# SensorStick.net
KiCad netlist of a schematic drawn in EAGLE
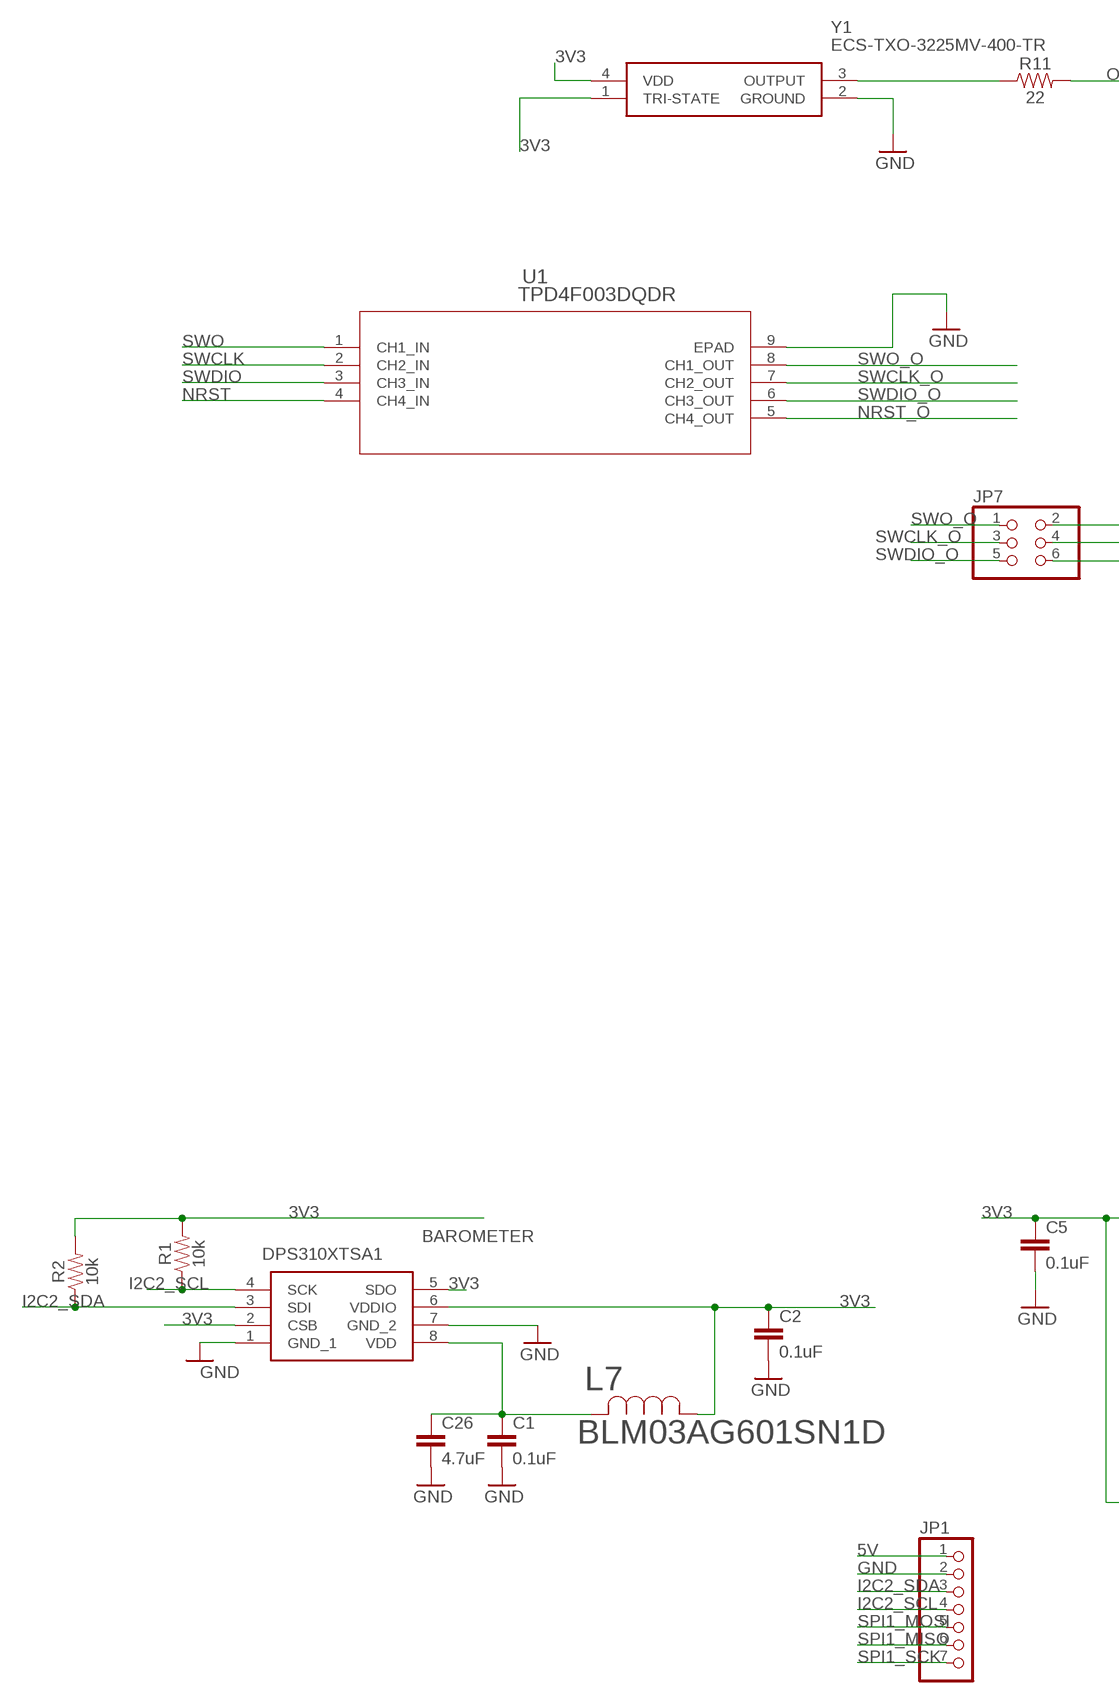
[diagram p0: schematic, sheet 1, part 1 of 2]
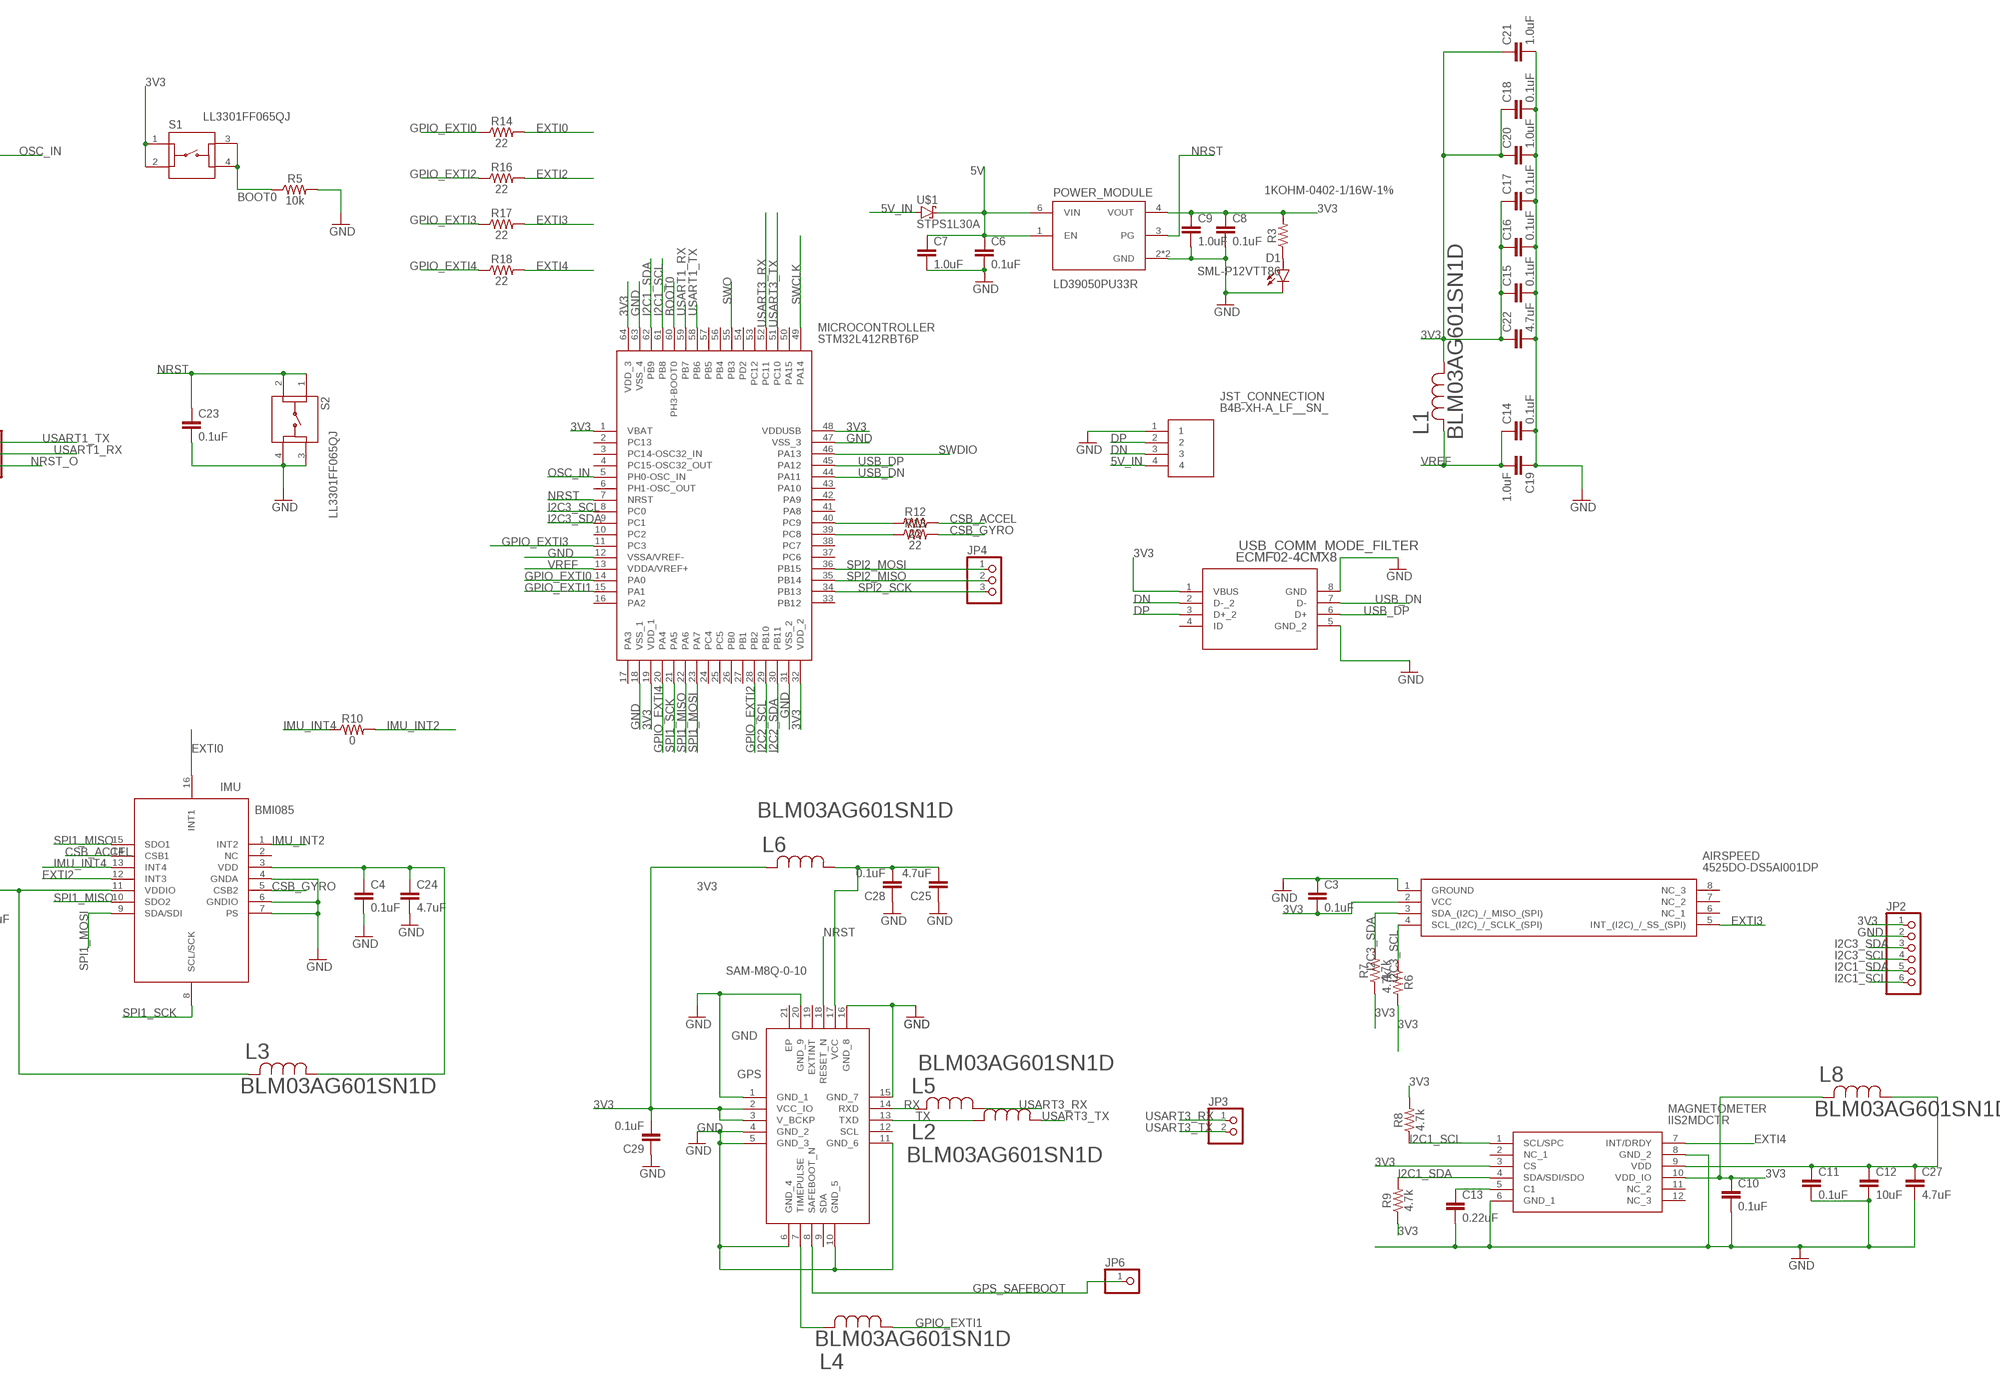
[diagram p1: schematic, sheet 1, part 2 of 2]

(export (version "E")
  (design (tool "Eeschema 10.0.6"))
  (components
    (comp (ref "AIRSPEED")
      (value "4525DO-DS5AI001DP")
      (footprint "eagle-import:4525DO-DS...P")
      (fields (field (name "MOUSER_PART_NUMBER") "824-4525DODS5AI001DP"))
      (libsource (lib "eagle-import") (part "4525DO-DS5AI001DP"))
    )
    (comp (ref "BAROMETER")
      (value "DPS310XTSA1")
      (footprint "eagle-import:DPS310XTSA1")
      (fields (field (name "MOUSER_PART_NUMBER") "726-DPS310XTSA1"))
      (libsource (lib "eagle-import") (part "DPS310XTSA1"))
    )
    (comp (ref "C1")
      (value "0.1uF")
      (footprint "eagle-import:0402")
      (libsource (lib "eagle-import") (part "0.1UF-0402-6.3V-10%-X7R"))
    )
    (comp (ref "C2")
      (value "0.1uF")
      (footprint "eagle-import:0402")
      (libsource (lib "eagle-import") (part "0.1UF-0402-6.3V-10%-X7R"))
    )
    (comp (ref "C3")
      (value "0.1uF")
      (footprint "eagle-import:0402")
      (fields (field (name "SPICEPREFIX") "C"))
      (libsource (lib "eagle-import") (part "0.1UF-0402-6.3V-10%-X7R"))
    )
    (comp (ref "C4")
      (value "0.1uF")
      (footprint "eagle-import:0402")
      (libsource (lib "eagle-import") (part "0.1UF-0402-6.3V-10%-X7R"))
    )
    (comp (ref "C5")
      (value "0.1uF")
      (footprint "eagle-import:0402")
      (libsource (lib "eagle-import") (part "0.1UF-0402-6.3V-10%-X7R"))
    )
    (comp (ref "C6")
      (value "0.1uF")
      (footprint "eagle-import:0402")
      (libsource (lib "eagle-import") (part "0.1UF-0402-6.3V-10%-X7R"))
    )
    (comp (ref "C7")
      (value "1.0uF")
      (footprint "eagle-import:0402")
      (libsource (lib "eagle-import") (part "1.0UF-0402-16V-10%"))
    )
    (comp (ref "C8")
      (value "0.1uF")
      (footprint "eagle-import:0402")
      (libsource (lib "eagle-import") (part "0.1UF-0402-6.3V-10%-X7R"))
    )
    (comp (ref "C9")
      (value "1.0uF")
      (footprint "eagle-import:0402")
      (libsource (lib "eagle-import") (part "1.0UF-0402-16V-10%"))
    )
    (comp (ref "C10")
      (value "0.1uF")
      (footprint "eagle-import:0402")
      (libsource (lib "eagle-import") (part "0.1UF-0402-6.3V-10%-X7R"))
    )
    (comp (ref "C11")
      (value "0.1uF")
      (footprint "eagle-import:0402")
      (libsource (lib "eagle-import") (part "0.1UF-0402-6.3V-10%-X7R"))
    )
    (comp (ref "C12")
      (value "10uF")
      (footprint "eagle-import:0603")
      (libsource (lib "eagle-import") (part "10UF-0603-6.3V-20%"))
    )
    (comp (ref "C13")
      (value "0.22uF")
      (footprint "eagle-import:0603")
      (libsource (lib "eagle-import") (part "0.22UF-0603-25V-10%"))
    )
    (comp (ref "C14")
      (value "0.1uF")
      (footprint "eagle-import:0603")
      (libsource (lib "eagle-import") (part "SparkFun-Capacitors_510_0.1UF-0603-25V-5%"))
    )
    (comp (ref "C15")
      (value "0.1uF")
      (footprint "eagle-import:0603")
      (libsource (lib "eagle-import") (part "SparkFun-Capacitors_510_0.1UF-0603-25V-5%"))
    )
    (comp (ref "C16")
      (value "0.1uF")
      (footprint "eagle-import:0603")
      (libsource (lib "eagle-import") (part "SparkFun-Capacitors_510_0.1UF-0603-25V-5%"))
    )
    (comp (ref "C17")
      (value "0.1uF")
      (footprint "eagle-import:0603")
      (libsource (lib "eagle-import") (part "SparkFun-Capacitors_510_0.1UF-0603-25V-5%"))
    )
    (comp (ref "C18")
      (value "0.1uF")
      (footprint "eagle-import:0603")
      (libsource (lib "eagle-import") (part "SparkFun-Capacitors_510_0.1UF-0603-25V-5%"))
    )
    (comp (ref "C19")
      (value "1.0uF")
      (footprint "eagle-import:0805")
      (libsource (lib "eagle-import") (part "SparkFun-Capacitors_510_1.0UF-0805-25V-10%"))
    )
    (comp (ref "C20")
      (value "1.0uF")
      (footprint "eagle-import:0805")
      (libsource (lib "eagle-import") (part "SparkFun-Capacitors_510_1.0UF-0805-25V-10%"))
    )
    (comp (ref "C21")
      (value "1.0uF")
      (footprint "eagle-import:0805")
      (libsource (lib "eagle-import") (part "SparkFun-Capacitors_510_1.0UF-0805-25V-10%"))
    )
    (comp (ref "C22")
      (value "4.7uF")
      (footprint "eagle-import:0603")
      (libsource (lib "eagle-import") (part "4.7UF0603"))
    )
    (comp (ref "C23")
      (value "0.1uF")
      (footprint "eagle-import:0603")
      (libsource (lib "eagle-import") (part "SparkFun-Capacitors_510_0.1UF-0603-25V-5%"))
    )
    (comp (ref "C24")
      (value "4.7uF")
      (footprint "eagle-import:0603")
      (libsource (lib "eagle-import") (part "4.7UF0603"))
    )
    (comp (ref "C25")
      (value "4.7uF")
      (footprint "eagle-import:0603")
      (libsource (lib "eagle-import") (part "4.7UF0603"))
    )
    (comp (ref "C26")
      (value "4.7uF")
      (footprint "eagle-import:0603")
      (libsource (lib "eagle-import") (part "4.7UF0603"))
    )
    (comp (ref "C27")
      (value "4.7uF")
      (footprint "eagle-import:0603")
      (libsource (lib "eagle-import") (part "4.7UF0603"))
    )
    (comp (ref "C28")
      (value "0.1uF")
      (footprint "eagle-import:0402")
      (libsource (lib "eagle-import") (part "SparkFun-Capacitors_510_0.1UF-0402-16V-10%"))
    )
    (comp (ref "C29")
      (value "0.1uF")
      (footprint "eagle-import:0402")
      (libsource (lib "eagle-import") (part "SparkFun-Capacitors_510_0.1UF-0402-16V-10%"))
    )
    (comp (ref "D1")
      (value "SML-P12VTT86")
      (footprint "eagle-import:LED_SML-P11UTT86R")
      (fields (field (name "MF") "Rohm"))
      (libsource (lib "eagle-import") (part "SML-P12VTT86"))
    )
    (comp (ref "GPS")
      (value "SAM-M8Q-0-10")
      (footprint "eagle-import:SAMM8Q010")
      (libsource (lib "eagle-import") (part "SAM-M8Q-0-10"))
    )
    (comp (ref "IMU")
      (value "BMI085")
      (footprint "eagle-import:BMI085")
      (fields (field (name "MOUSER_PART_NUMBER") "262-BMI085"))
      (libsource (lib "eagle-import") (part "BMI085"))
    )
    (comp (ref "JP1")
      (value "PINHD-1X7")
      (footprint "eagle-import:1X07")
      (libsource (lib "eagle-import") (part "PINHD-1X7"))
    )
    (comp (ref "JP2")
      (value "PINHD-1X6")
      (footprint "eagle-import:1X06")
      (libsource (lib "eagle-import") (part "PINHD-1X6"))
    )
    (comp (ref "JP3")
      (value "PINHD-1X2")
      (footprint "eagle-import:1X02")
      (libsource (lib "eagle-import") (part "PINHD-1X2"))
    )
    (comp (ref "JP4")
      (value "PINHD-1X3")
      (footprint "eagle-import:1X03")
      (libsource (lib "eagle-import") (part "PINHD-1X3"))
    )
    (comp (ref "JP6")
      (value "PINHD-1X1")
      (footprint "eagle-import:1X01")
      (libsource (lib "eagle-import") (part "PINHD-1X1"))
    )
    (comp (ref "JP7")
      (value "PINHD-2X3")
      (footprint "eagle-import:2X03")
      (libsource (lib "eagle-import") (part "PINHD-2X3"))
    )
    (comp (ref "JST_CONNECTION")
      (value "B4B-XH-A_LF__SN_")
      (footprint "eagle-import:B4BXHALFSN")
      (fields (field (name "ARROW_PART_NUMBER") "B4B-XH-A(LF)(SN)"))
      (libsource (lib "eagle-import") (part "B4B-XH-A_LF__SN_"))
    )
    (comp (ref "L1")
      (value "BLM03AG601SN1D")
      (footprint "eagle-import:IND_BLM03_0201_MUR")
      (fields (field (name "COPYRIGHT") "Copyright (C) 2023 Ultra Librarian. All rights reserved."))
      (libsource (lib "eagle-import") (part "BLM03AG601SN1D"))
    )
    (comp (ref "L2")
      (value "BLM03AG601SN1D")
      (footprint "eagle-import:IND_BLM03_0201_MUR")
      (fields (field (name "COPYRIGHT") "Copyright (C) 2023 Ultra Librarian. All rights reserved."))
      (libsource (lib "eagle-import") (part "BLM03AG601SN1D"))
    )
    (comp (ref "L3")
      (value "BLM03AG601SN1D")
      (footprint "eagle-import:IND_BLM03_0201_MUR")
      (fields (field (name "COPYRIGHT") "Copyright (C) 2023 Ultra Librarian. All rights reserved."))
      (libsource (lib "eagle-import") (part "BLM03AG601SN1D"))
    )
    (comp (ref "L4")
      (value "BLM03AG601SN1D")
      (footprint "eagle-import:IND_BLM03_0201_MUR")
      (fields (field (name "COPYRIGHT") "Copyright (C) 2023 Ultra Librarian. All rights reserved."))
      (libsource (lib "eagle-import") (part "BLM03AG601SN1D"))
    )
    (comp (ref "L5")
      (value "BLM03AG601SN1D")
      (footprint "eagle-import:IND_BLM03_0201_MUR")
      (fields (field (name "COPYRIGHT") "Copyright (C) 2023 Ultra Librarian. All rights reserved."))
      (libsource (lib "eagle-import") (part "BLM03AG601SN1D"))
    )
    (comp (ref "L6")
      (value "BLM03AG601SN1D")
      (footprint "eagle-import:IND_BLM03_0201_MUR")
      (fields (field (name "COPYRIGHT") "Copyright (C) 2023 Ultra Librarian. All rights reserved."))
      (libsource (lib "eagle-import") (part "BLM03AG601SN1D"))
    )
    (comp (ref "L7")
      (value "BLM03AG601SN1D")
      (footprint "eagle-import:IND_BLM03_0201_MUR")
      (fields (field (name "COPYRIGHT") "Copyright (C) 2023 Ultra Librarian. All rights reserved."))
      (libsource (lib "eagle-import") (part "BLM03AG601SN1D"))
    )
    (comp (ref "L8")
      (value "BLM03AG601SN1D")
      (footprint "eagle-import:IND_BLM03_0201_MUR")
      (fields (field (name "COPYRIGHT") "Copyright (C) 2023 Ultra Librarian. All rights reserved."))
      (libsource (lib "eagle-import") (part "BLM03AG601SN1D"))
    )
    (comp (ref "MAGNETOMETER")
      (value "IIS2MDCTR")
      (footprint "eagle-import:IIS2MDCTR")
      (fields (field (name "MOUSER_PART_NUMBER") "511-IIS2MDCTR"))
      (libsource (lib "eagle-import") (part "IIS2MDCTR"))
    )
    (comp (ref "MICROCONTROLLER")
      (value "STM32L412RBT6P")
      (footprint "eagle-import:QFP50P1200X1200X160-64N")
      (fields (field (name "MOUSER_PART_NUMBER") "511-STM32L412RBT6P"))
      (libsource (lib "eagle-import") (part "STM32L412RBT6P"))
    )
    (comp (ref "POWER_MODULE")
      (value "LD39050PU33R")
      (footprint "eagle-import:SON95P300X300X100-7N")
      (fields (field (name "MF") "STMicroelectronics"))
      (libsource (lib "eagle-import") (part "LD39050PU33R"))
    )
    (comp (ref "R1")
      (value "10k")
      (footprint "eagle-import:0402")
      (libsource (lib "eagle-import") (part "10KOHM-0402-1/16W-1%"))
    )
    (comp (ref "R2")
      (value "10k")
      (footprint "eagle-import:0402")
      (libsource (lib "eagle-import") (part "10KOHM-0402-1/16W-1%"))
    )
    (comp (ref "R3")
      (value "1KOHM-0402-1/16W-1%")
      (footprint "eagle-import:0402")
      (libsource (lib "eagle-import") (part "1KOHM-0402-1/16W-1%"))
    )
    (comp (ref "R5")
      (value "10k")
      (footprint "eagle-import:0603")
      (libsource (lib "eagle-import") (part "SparkFun-Resistors_532_10KOHM-0603-1/10W-1%"))
    )
    (comp (ref "R6")
      (value "4.7k")
      (footprint "eagle-import:0603")
      (libsource (lib "eagle-import") (part "4.7KOHM-0603-1/10W-1%"))
    )
    (comp (ref "R7")
      (value "4.7k")
      (footprint "eagle-import:0603")
      (libsource (lib "eagle-import") (part "4.7KOHM-0603-1/10W-1%"))
    )
    (comp (ref "R8")
      (value "4.7k")
      (footprint "eagle-import:0603")
      (libsource (lib "eagle-import") (part "4.7KOHM-0603-1/10W-1%"))
    )
    (comp (ref "R9")
      (value "4.7k")
      (footprint "eagle-import:0603")
      (libsource (lib "eagle-import") (part "4.7KOHM-0603-1/10W-1%"))
    )
    (comp (ref "R10")
      (value "0")
      (footprint "eagle-import:0603")
      (libsource (lib "eagle-import") (part "0OHM-0603-1/10W-5%"))
    )
    (comp (ref "R11")
      (value "22")
      (footprint "eagle-import:0402")
      (libsource (lib "eagle-import") (part "22OHM-0402-1/10W-1%"))
    )
    (comp (ref "R12")
      (value "22")
      (footprint "eagle-import:0402")
      (libsource (lib "eagle-import") (part "22OHM-0402-1/10W-1%"))
    )
    (comp (ref "R13")
      (value "22")
      (footprint "eagle-import:0402")
      (libsource (lib "eagle-import") (part "22OHM-0402-1/10W-1%"))
    )
    (comp (ref "R14")
      (value "22")
      (footprint "eagle-import:0402")
      (libsource (lib "eagle-import") (part "22OHM-0402-1/10W-1%"))
    )
    (comp (ref "R16")
      (value "22")
      (footprint "eagle-import:0402")
      (libsource (lib "eagle-import") (part "22OHM-0402-1/10W-1%"))
    )
    (comp (ref "R17")
      (value "22")
      (footprint "eagle-import:0402")
      (libsource (lib "eagle-import") (part "22OHM-0402-1/10W-1%"))
    )
    (comp (ref "R18")
      (value "22")
      (footprint "eagle-import:0402")
      (libsource (lib "eagle-import") (part "22OHM-0402-1/10W-1%"))
    )
    (comp (ref "S1")
      (value "LL3301FF065QJ")
      (footprint "eagle-import:LL3301FF065QJ")
      (fields (field (name "MOUSER_PART_NUMBER") "612-LL3301FF065QJ"))
      (libsource (lib "eagle-import") (part "LL3301FF065QJ"))
    )
    (comp (ref "S2")
      (value "LL3301FF065QJ")
      (footprint "eagle-import:LL3301FF065QJ")
      (fields (field (name "MOUSER_PART_NUMBER") "612-LL3301FF065QJ"))
      (libsource (lib "eagle-import") (part "LL3301FF065QJ"))
    )
    (comp (ref "U$1")
      (value "STPS1L30A")
      (footprint "eagle-import:DIOM5226X223N")
      (libsource (lib "eagle-import") (part "STPS1L30A"))
    )
    (comp (ref "U1")
      (value "TPD4F003DQDR")
      (footprint "eagle-import:DQD8_1P2X0P4")
      (fields (field (name "COPYRIGHT") "Copyright (C) 2023 Ultra Librarian. All rights reserved."))
      (libsource (lib "eagle-import") (part "TPD4F003DQDR"))
    )
    (comp (ref "USB_COMM_MODE_FILTER")
      (value "ECMF02-4CMX8")
      (footprint "eagle-import:MICRO_QFN-8L_STM")
      (fields (field (name "COPYRIGHT") "Copyright (C) 2023 Ultra Librarian. All rights reserved."))
      (libsource (lib "eagle-import") (part "ECMF02-4CMX8"))
    )
    (comp (ref "Y1")
      (value "ECS-TXO-3225MV-400-TR")
      (footprint "eagle-import:ECSTXO3225MV400TR")
      (libsource (lib "eagle-import") (part "ECS-TXO-3225MV-400-TR"))
    )
  )
  (nets
    (net (code "1") (name "/3V3") (class "Default")
      (node (ref "AIRSPEED") (pin "2") (pinfunction "VCC_2") (pintype "power_in"))
      (node (ref "BAROMETER") (pin "2") (pinfunction "CSB_2") (pintype "bidirectional"))
      (node (ref "BAROMETER") (pin "5") (pinfunction "SDO_5") (pintype "bidirectional"))
      (node (ref "BAROMETER") (pin "6") (pinfunction "VDDIO_6") (pintype "bidirectional"))
      (node (ref "C10") (pin "1") (pinfunction "1_1") (pintype "passive"))
      (node (ref "C15") (pin "1") (pinfunction "1_1") (pintype "passive"))
      (node (ref "C16") (pin "1") (pinfunction "1_1") (pintype "passive"))
      (node (ref "C17") (pin "1") (pinfunction "1_1") (pintype "passive"))
      (node (ref "C18") (pin "1") (pinfunction "1_1") (pintype "passive"))
      (node (ref "C2") (pin "1") (pinfunction "1_1") (pintype "passive"))
      (node (ref "C20") (pin "1") (pinfunction "1_1") (pintype "passive"))
      (node (ref "C21") (pin "1") (pinfunction "1_1") (pintype "passive"))
      (node (ref "C22") (pin "1") (pinfunction "1_1") (pintype "passive"))
      (node (ref "C29") (pin "2") (pinfunction "2_2") (pintype "passive"))
      (node (ref "C3") (pin "2") (pinfunction "2_2") (pintype "passive"))
      (node (ref "C5") (pin "1") (pinfunction "1_1") (pintype "passive"))
      (node (ref "C8") (pin "1") (pinfunction "1_1") (pintype "passive"))
      (node (ref "C9") (pin "1") (pinfunction "1_1") (pintype "passive"))
      (node (ref "GPS") (pin "2") (pinfunction "VCC_IO_2") (pintype "bidirectional"))
      (node (ref "GPS") (pin "3") (pinfunction "V_BCKP_3") (pintype "bidirectional"))
      (node (ref "IMU") (pin "11") (pinfunction "VDDIO_11") (pintype "bidirectional"))
      (node (ref "JP2") (pin "1") (pinfunction "1_1") (pintype "passive"))
      (node (ref "L1") (pin "1") (pinfunction "1_1") (pintype "passive"))
      (node (ref "L3") (pin "2") (pinfunction "2_2") (pintype "passive"))
      (node (ref "L6") (pin "2") (pinfunction "2_2") (pintype "passive"))
      (node (ref "L7") (pin "1") (pinfunction "1_1") (pintype "passive"))
      (node (ref "L8") (pin "2") (pinfunction "2_2") (pintype "passive"))
      (node (ref "MAGNETOMETER") (pin "10") (pinfunction "VDD_IO_10") (pintype "bidirectional"))
      (node (ref "MAGNETOMETER") (pin "3") (pinfunction "CS_3") (pintype "bidirectional"))
      (node (ref "MICROCONTROLLER") (pin "1") (pinfunction "VBAT_1") (pintype "bidirectional"))
      (node (ref "MICROCONTROLLER") (pin "19") (pinfunction "VDD_1_19") (pintype "bidirectional"))
      (node (ref "MICROCONTROLLER") (pin "32") (pinfunction "VDD_2_32") (pintype "bidirectional"))
      (node (ref "MICROCONTROLLER") (pin "48") (pinfunction "VDDUSB_48") (pintype "bidirectional"))
      (node (ref "MICROCONTROLLER") (pin "64") (pinfunction "VDD_3_64") (pintype "bidirectional"))
      (node (ref "POWER_MODULE") (pin "4") (pinfunction "VOUT_4") (pintype "output"))
      (node (ref "R1") (pin "2") (pinfunction "2_2") (pintype "passive"))
      (node (ref "R2") (pin "2") (pinfunction "2_2") (pintype "passive"))
      (node (ref "R3") (pin "2") (pinfunction "2_2") (pintype "passive"))
      (node (ref "R6") (pin "2") (pinfunction "2_2") (pintype "passive"))
      (node (ref "R7") (pin "1") (pinfunction "1_1") (pintype "passive"))
      (node (ref "R8") (pin "2") (pinfunction "2_2") (pintype "passive"))
      (node (ref "R9") (pin "1") (pinfunction "1_1") (pintype "passive"))
      (node (ref "S1") (pin "1") (pinfunction "1_1") (pintype "passive"))
      (node (ref "S1") (pin "2") (pinfunction "2_2") (pintype "passive"))
      (node (ref "USB_COMM_MODE_FILTER") (pin "1") (pinfunction "VBUS_1") (pintype "power_in"))
      (node (ref "Y1") (pin "1") (pinfunction "TRI-STATE_1") (pintype "bidirectional"))
      (node (ref "Y1") (pin "4") (pinfunction "VDD_4") (pintype "bidirectional"))
    )
    (net (code "2") (name "/5V") (class "Default")
      (node (ref "C6") (pin "1") (pinfunction "1_1") (pintype "passive"))
      (node (ref "C7") (pin "1") (pinfunction "1_1") (pintype "passive"))
      (node (ref "JP1") (pin "1") (pinfunction "1_1") (pintype "passive"))
      (node (ref "POWER_MODULE") (pin "1") (pinfunction "EN_1") (pintype "input"))
      (node (ref "POWER_MODULE") (pin "6") (pinfunction "VIN_6") (pintype "power_in"))
      (node (ref "U$1") (pin "1") (pinfunction "C_1") (pintype "passive"))
    )
    (net (code "3") (name "/5V_IN") (class "Default")
      (node (ref "JST_CONNECTION") (pin "4") (pinfunction "4_4") (pintype "bidirectional"))
      (node (ref "U$1") (pin "2") (pinfunction "A_2") (pintype "passive"))
    )
    (net (code "4") (name "/BOOT0") (class "Default")
      (node (ref "MICROCONTROLLER") (pin "60") (pinfunction "PH3-BOOT0_60") (pintype "bidirectional"))
      (node (ref "R5") (pin "1") (pinfunction "1_1") (pintype "passive"))
      (node (ref "S1") (pin "3") (pinfunction "3_3") (pintype "passive"))
      (node (ref "S1") (pin "4") (pinfunction "4_4") (pintype "passive"))
    )
    (net (code "5") (name "/CSB_ACCEL") (class "Default")
      (node (ref "IMU") (pin "14") (pinfunction "CSB1_14") (pintype "bidirectional"))
      (node (ref "R12") (pin "2") (pinfunction "2_2") (pintype "passive"))
    )
    (net (code "6") (name "/CSB_GYRO") (class "Default")
      (node (ref "IMU") (pin "5") (pinfunction "CSB2_5") (pintype "bidirectional"))
      (node (ref "R13") (pin "2") (pinfunction "2_2") (pintype "passive"))
    )
    (net (code "7") (name "/DN") (class "Default")
      (node (ref "JST_CONNECTION") (pin "3") (pinfunction "3_3") (pintype "bidirectional"))
      (node (ref "USB_COMM_MODE_FILTER") (pin "2") (pinfunction "D-_2_2") (pintype "bidirectional"))
    )
    (net (code "8") (name "/DP") (class "Default")
      (node (ref "JST_CONNECTION") (pin "2") (pinfunction "2_2") (pintype "bidirectional"))
      (node (ref "USB_COMM_MODE_FILTER") (pin "3") (pinfunction "D+_2_3") (pintype "bidirectional"))
    )
    (net (code "9") (name "/EXTI0") (class "Default")
      (node (ref "IMU") (pin "16") (pinfunction "INT1_16") (pintype "bidirectional"))
      (node (ref "R14") (pin "2") (pinfunction "2_2") (pintype "passive"))
    )
    (net (code "10") (name "/EXTI2") (class "Default")
      (node (ref "IMU") (pin "12") (pinfunction "INT3_12") (pintype "bidirectional"))
      (node (ref "R16") (pin "2") (pinfunction "2_2") (pintype "passive"))
    )
    (net (code "11") (name "/EXTI3") (class "Default")
      (node (ref "AIRSPEED") (pin "5") (pinfunction "INT_(I2C)_/_SS_(SPI)_5") (pintype "bidirectional"))
      (node (ref "R17") (pin "2") (pinfunction "2_2") (pintype "passive"))
    )
    (net (code "12") (name "/EXTI4") (class "Default")
      (node (ref "MAGNETOMETER") (pin "7") (pinfunction "INT/DRDY_7") (pintype "bidirectional"))
      (node (ref "R18") (pin "2") (pinfunction "2_2") (pintype "passive"))
    )
    (net (code "13") (name "/GPIO_EXTI0") (class "Default")
      (node (ref "MICROCONTROLLER") (pin "14") (pinfunction "PA0_14") (pintype "bidirectional"))
      (node (ref "R14") (pin "1") (pinfunction "1_1") (pintype "passive"))
    )
    (net (code "14") (name "/GPIO_EXTI1") (class "Default")
      (node (ref "L4") (pin "1") (pinfunction "1_1") (pintype "passive"))
      (node (ref "MICROCONTROLLER") (pin "15") (pinfunction "PA1_15") (pintype "bidirectional"))
    )
    (net (code "15") (name "/GPIO_EXTI2") (class "Default")
      (node (ref "MICROCONTROLLER") (pin "28") (pinfunction "PB2_28") (pintype "bidirectional"))
      (node (ref "R16") (pin "1") (pinfunction "1_1") (pintype "passive"))
    )
    (net (code "16") (name "/GPIO_EXTI3") (class "Default")
      (node (ref "MICROCONTROLLER") (pin "11") (pinfunction "PC3_11") (pintype "bidirectional"))
      (node (ref "R17") (pin "1") (pinfunction "1_1") (pintype "passive"))
    )
    (net (code "17") (name "/GPIO_EXTI4") (class "Default")
      (node (ref "MICROCONTROLLER") (pin "20") (pinfunction "PA4_20") (pintype "bidirectional"))
      (node (ref "R18") (pin "1") (pinfunction "1_1") (pintype "passive"))
    )
    (net (code "18") (name "/GPS_SAFEBOOT") (class "Default")
      (node (ref "GPS") (pin "8") (pinfunction "SAFEBOOT_N_8") (pintype "bidirectional"))
      (node (ref "JP6") (pin "1") (pinfunction "1_1") (pintype "passive"))
    )
    (net (code "19") (name "/I2C1_SCL") (class "Default")
      (node (ref "JP2") (pin "6") (pinfunction "6_6") (pintype "passive"))
      (node (ref "MAGNETOMETER") (pin "1") (pinfunction "SCL/SPC_1") (pintype "bidirectional"))
      (node (ref "MICROCONTROLLER") (pin "61") (pinfunction "PB8_61") (pintype "bidirectional"))
      (node (ref "R8") (pin "1") (pinfunction "1_1") (pintype "passive"))
    )
    (net (code "20") (name "/I2C1_SDA") (class "Default")
      (node (ref "JP2") (pin "5") (pinfunction "5_5") (pintype "passive"))
      (node (ref "MAGNETOMETER") (pin "4") (pinfunction "SDA/SDI/SDO_4") (pintype "bidirectional"))
      (node (ref "MICROCONTROLLER") (pin "62") (pinfunction "PB9_62") (pintype "bidirectional"))
      (node (ref "R9") (pin "2") (pinfunction "2_2") (pintype "passive"))
    )
    (net (code "21") (name "/I2C2_SCL") (class "Default")
      (node (ref "BAROMETER") (pin "4") (pinfunction "SCK_4") (pintype "bidirectional"))
      (node (ref "JP1") (pin "4") (pinfunction "4_4") (pintype "passive"))
      (node (ref "MICROCONTROLLER") (pin "29") (pinfunction "PB10_29") (pintype "bidirectional"))
      (node (ref "R1") (pin "1") (pinfunction "1_1") (pintype "passive"))
    )
    (net (code "22") (name "/I2C2_SDA") (class "Default")
      (node (ref "BAROMETER") (pin "3") (pinfunction "SDI_3") (pintype "bidirectional"))
      (node (ref "JP1") (pin "3") (pinfunction "3_3") (pintype "passive"))
      (node (ref "MICROCONTROLLER") (pin "30") (pinfunction "PB11_30") (pintype "bidirectional"))
      (node (ref "R2") (pin "1") (pinfunction "1_1") (pintype "passive"))
    )
    (net (code "23") (name "/I2C3_SCL") (class "Default")
      (node (ref "AIRSPEED") (pin "4") (pinfunction "SCL_(I2C)_/_SCLK_(SPI)_4") (pintype "bidirectional"))
      (node (ref "JP2") (pin "4") (pinfunction "4_4") (pintype "passive"))
      (node (ref "MICROCONTROLLER") (pin "8") (pinfunction "PC0_8") (pintype "bidirectional"))
      (node (ref "R6") (pin "1") (pinfunction "1_1") (pintype "passive"))
    )
    (net (code "24") (name "/I2C3_SDA") (class "Default")
      (node (ref "AIRSPEED") (pin "3") (pinfunction "SDA_(I2C)_/_MISO_(SPI)_3") (pintype "bidirectional"))
      (node (ref "JP2") (pin "3") (pinfunction "3_3") (pintype "passive"))
      (node (ref "MICROCONTROLLER") (pin "9") (pinfunction "PC1_9") (pintype "bidirectional"))
      (node (ref "R7") (pin "2") (pinfunction "2_2") (pintype "passive"))
    )
    (net (code "25") (name "/IMU_INT2") (class "Default")
      (node (ref "IMU") (pin "1") (pinfunction "INT2_1") (pintype "bidirectional"))
      (node (ref "R10") (pin "2") (pinfunction "2_2") (pintype "passive"))
    )
    (net (code "26") (name "/IMU_INT4") (class "Default")
      (node (ref "IMU") (pin "13") (pinfunction "INT4_13") (pintype "bidirectional"))
      (node (ref "R10") (pin "1") (pinfunction "1_1") (pintype "passive"))
    )
    (net (code "27") (name "/NRST") (class "Default")
      (node (ref "C23") (pin "1") (pinfunction "1_1") (pintype "passive"))
      (node (ref "GPS") (pin "18") (pinfunction "RESET_N_18") (pintype "bidirectional"))
      (node (ref "MICROCONTROLLER") (pin "7") (pinfunction "NRST_7") (pintype "bidirectional"))
      (node (ref "POWER_MODULE") (pin "3") (pinfunction "PG_3") (pintype "bidirectional"))
      (node (ref "S2") (pin "1") (pinfunction "1_1") (pintype "passive"))
      (node (ref "S2") (pin "2") (pinfunction "2_2") (pintype "passive"))
      (node (ref "U1") (pin "4") (pinfunction "CH4_IN_4") (pintype "input"))
    )
    (net (code "28") (name "/NRST_O") (class "Default")
      (node (ref "JP7") (pin "6") (pinfunction "6_6") (pintype "passive"))
      (node (ref "U1") (pin "5") (pinfunction "CH4_OUT_5") (pintype "output"))
    )
    (net (code "29") (name "/OSC_IN") (class "Default")
      (node (ref "MICROCONTROLLER") (pin "5") (pinfunction "PH0-OSC_IN_5") (pintype "bidirectional"))
      (node (ref "R11") (pin "2") (pinfunction "2_2") (pintype "passive"))
    )
    (net (code "30") (name "/RX") (class "Default")
      (node (ref "GPS") (pin "14") (pinfunction "RXD_14") (pintype "bidirectional"))
      (node (ref "L5") (pin "2") (pinfunction "2_2") (pintype "passive"))
    )
    (net (code "31") (name "/SPI1_MISO") (class "Default")
      (node (ref "IMU") (pin "10") (pinfunction "SDO2_10") (pintype "bidirectional"))
      (node (ref "IMU") (pin "15") (pinfunction "SDO1_15") (pintype "bidirectional"))
      (node (ref "JP1") (pin "6") (pinfunction "6_6") (pintype "passive"))
      (node (ref "MICROCONTROLLER") (pin "22") (pinfunction "PA6_22") (pintype "bidirectional"))
    )
    (net (code "32") (name "/SPI1_MOSI") (class "Default")
      (node (ref "IMU") (pin "9") (pinfunction "SDA/SDI_9") (pintype "bidirectional"))
      (node (ref "JP1") (pin "5") (pinfunction "5_5") (pintype "passive"))
      (node (ref "MICROCONTROLLER") (pin "23") (pinfunction "PA7_23") (pintype "bidirectional"))
    )
    (net (code "33") (name "/SPI1_SCK") (class "Default")
      (node (ref "IMU") (pin "8") (pinfunction "SCL/SCK_8") (pintype "bidirectional"))
      (node (ref "JP1") (pin "7") (pinfunction "7_7") (pintype "passive"))
      (node (ref "MICROCONTROLLER") (pin "21") (pinfunction "PA5_21") (pintype "bidirectional"))
    )
    (net (code "34") (name "/SPI2_MISO") (class "Default")
      (node (ref "JP4") (pin "2") (pinfunction "2_2") (pintype "passive"))
      (node (ref "MICROCONTROLLER") (pin "35") (pinfunction "PB14_35") (pintype "bidirectional"))
    )
    (net (code "35") (name "/SPI2_MOSI") (class "Default")
      (node (ref "JP4") (pin "1") (pinfunction "1_1") (pintype "passive"))
      (node (ref "MICROCONTROLLER") (pin "36") (pinfunction "PB15_36") (pintype "bidirectional"))
    )
    (net (code "36") (name "/SPI2_SCK") (class "Default")
      (node (ref "JP4") (pin "3") (pinfunction "3_3") (pintype "passive"))
      (node (ref "MICROCONTROLLER") (pin "34") (pinfunction "PB13_34") (pintype "bidirectional"))
    )
    (net (code "37") (name "/SWCLK") (class "Default")
      (node (ref "MICROCONTROLLER") (pin "49") (pinfunction "PA14_49") (pintype "bidirectional"))
      (node (ref "U1") (pin "2") (pinfunction "CH2_IN_2") (pintype "input"))
    )
    (net (code "38") (name "/SWCLK_O") (class "Default")
      (node (ref "JP7") (pin "3") (pinfunction "3_3") (pintype "passive"))
      (node (ref "U1") (pin "7") (pinfunction "CH2_OUT_7") (pintype "output"))
    )
    (net (code "39") (name "/SWDIO") (class "Default")
      (node (ref "MICROCONTROLLER") (pin "46") (pinfunction "PA13_46") (pintype "bidirectional"))
      (node (ref "U1") (pin "3") (pinfunction "CH3_IN_3") (pintype "input"))
    )
    (net (code "40") (name "/SWDIO_O") (class "Default")
      (node (ref "JP7") (pin "5") (pinfunction "5_5") (pintype "passive"))
      (node (ref "U1") (pin "6") (pinfunction "CH3_OUT_6") (pintype "output"))
    )
    (net (code "41") (name "/SWO") (class "Default")
      (node (ref "MICROCONTROLLER") (pin "55") (pinfunction "PB3_55") (pintype "bidirectional"))
      (node (ref "U1") (pin "1") (pinfunction "CH1_IN_1") (pintype "input"))
    )
    (net (code "42") (name "/SWO_O") (class "Default")
      (node (ref "JP7") (pin "1") (pinfunction "1_1") (pintype "passive"))
      (node (ref "U1") (pin "8") (pinfunction "CH1_OUT_8") (pintype "output"))
    )
    (net (code "43") (name "/TX") (class "Default")
      (node (ref "GPS") (pin "13") (pinfunction "TXD_13") (pintype "bidirectional"))
      (node (ref "L2") (pin "2") (pinfunction "2_2") (pintype "passive"))
    )
    (net (code "44") (name "/USART1_RX") (class "Default")
      (node (ref "JP7") (pin "4") (pinfunction "4_4") (pintype "passive"))
      (node (ref "MICROCONTROLLER") (pin "59") (pinfunction "PB7_59") (pintype "bidirectional"))
    )
    (net (code "45") (name "/USART1_TX") (class "Default")
      (node (ref "JP7") (pin "2") (pinfunction "2_2") (pintype "passive"))
      (node (ref "MICROCONTROLLER") (pin "58") (pinfunction "PB6_58") (pintype "bidirectional"))
    )
    (net (code "46") (name "/USART3_RX") (class "Default")
      (node (ref "JP3") (pin "1") (pinfunction "1_1") (pintype "passive"))
      (node (ref "L5") (pin "1") (pinfunction "1_1") (pintype "passive"))
      (node (ref "MICROCONTROLLER") (pin "52") (pinfunction "PC11_52") (pintype "bidirectional"))
    )
    (net (code "47") (name "/USART3_TX") (class "Default")
      (node (ref "JP3") (pin "2") (pinfunction "2_2") (pintype "passive"))
      (node (ref "L2") (pin "1") (pinfunction "1_1") (pintype "passive"))
      (node (ref "MICROCONTROLLER") (pin "51") (pinfunction "PC10_51") (pintype "bidirectional"))
    )
    (net (code "48") (name "/USB_DN") (class "Default")
      (node (ref "MICROCONTROLLER") (pin "44") (pinfunction "PA11_44") (pintype "bidirectional"))
      (node (ref "USB_COMM_MODE_FILTER") (pin "7") (pinfunction "D-_7") (pintype "bidirectional"))
    )
    (net (code "49") (name "/USB_DP") (class "Default")
      (node (ref "MICROCONTROLLER") (pin "45") (pinfunction "PA12_45") (pintype "bidirectional"))
      (node (ref "USB_COMM_MODE_FILTER") (pin "6") (pinfunction "D+_6") (pintype "bidirectional"))
    )
    (net (code "50") (name "/VREF") (class "Default")
      (node (ref "C14") (pin "1") (pinfunction "1_1") (pintype "passive"))
      (node (ref "C19") (pin "2") (pinfunction "2_2") (pintype "passive"))
      (node (ref "L1") (pin "2") (pinfunction "2_2") (pintype "passive"))
      (node (ref "MICROCONTROLLER") (pin "13") (pinfunction "VDDA/VREF+_13") (pintype "bidirectional"))
    )
    (net (code "51") (name "GND") (class "Default")
      (node (ref "AIRSPEED") (pin "1") (pinfunction "GROUND_1") (pintype "power_in"))
      (node (ref "BAROMETER") (pin "1") (pinfunction "GND_1_1") (pintype "bidirectional"))
      (node (ref "BAROMETER") (pin "7") (pinfunction "GND_2_7") (pintype "bidirectional"))
      (node (ref "C1") (pin "2") (pinfunction "2_2") (pintype "passive"))
      (node (ref "C10") (pin "2") (pinfunction "2_2") (pintype "passive"))
      (node (ref "C11") (pin "2") (pinfunction "2_2") (pintype "passive"))
      (node (ref "C12") (pin "2") (pinfunction "2_2") (pintype "passive"))
      (node (ref "C13") (pin "2") (pinfunction "2_2") (pintype "passive"))
      (node (ref "C14") (pin "2") (pinfunction "2_2") (pintype "passive"))
      (node (ref "C15") (pin "2") (pinfunction "2_2") (pintype "passive"))
      (node (ref "C16") (pin "2") (pinfunction "2_2") (pintype "passive"))
      (node (ref "C17") (pin "2") (pinfunction "2_2") (pintype "passive"))
      (node (ref "C18") (pin "2") (pinfunction "2_2") (pintype "passive"))
      (node (ref "C19") (pin "1") (pinfunction "1_1") (pintype "passive"))
      (node (ref "C2") (pin "2") (pinfunction "2_2") (pintype "passive"))
      (node (ref "C20") (pin "2") (pinfunction "2_2") (pintype "passive"))
      (node (ref "C21") (pin "2") (pinfunction "2_2") (pintype "passive"))
      (node (ref "C22") (pin "2") (pinfunction "2_2") (pintype "passive"))
      (node (ref "C23") (pin "2") (pinfunction "2_2") (pintype "passive"))
      (node (ref "C24") (pin "2") (pinfunction "2_2") (pintype "passive"))
      (node (ref "C25") (pin "1") (pinfunction "1_1") (pintype "passive"))
      (node (ref "C26") (pin "2") (pinfunction "2_2") (pintype "passive"))
      (node (ref "C27") (pin "2") (pinfunction "2_2") (pintype "passive"))
      (node (ref "C28") (pin "1") (pinfunction "1_1") (pintype "passive"))
      (node (ref "C29") (pin "1") (pinfunction "1_1") (pintype "passive"))
      (node (ref "C3") (pin "1") (pinfunction "1_1") (pintype "passive"))
      (node (ref "C4") (pin "2") (pinfunction "2_2") (pintype "passive"))
      (node (ref "C5") (pin "2") (pinfunction "2_2") (pintype "passive"))
      (node (ref "C6") (pin "2") (pinfunction "2_2") (pintype "passive"))
      (node (ref "C7") (pin "2") (pinfunction "2_2") (pintype "passive"))
      (node (ref "C8") (pin "2") (pinfunction "2_2") (pintype "passive"))
      (node (ref "C9") (pin "2") (pinfunction "2_2") (pintype "passive"))
      (node (ref "D1") (pin "C") (pinfunction "C_C") (pintype "passive"))
      (node (ref "GPS") (pin "1") (pinfunction "GND_1_1") (pintype "bidirectional"))
      (node (ref "GPS") (pin "10") (pinfunction "GND_5_10") (pintype "bidirectional"))
      (node (ref "GPS") (pin "11") (pinfunction "GND_6_11") (pintype "bidirectional"))
      (node (ref "GPS") (pin "15") (pinfunction "GND_7_15") (pintype "bidirectional"))
      (node (ref "GPS") (pin "16") (pinfunction "GND_8_16") (pintype "bidirectional"))
      (node (ref "GPS") (pin "20") (pinfunction "GND_9_20") (pintype "bidirectional"))
      (node (ref "GPS") (pin "4") (pinfunction "GND_2_4") (pintype "bidirectional"))
      (node (ref "GPS") (pin "5") (pinfunction "GND_3_5") (pintype "bidirectional"))
      (node (ref "GPS") (pin "6") (pinfunction "GND_4_6") (pintype "bidirectional"))
      (node (ref "IMU") (pin "4") (pinfunction "GNDA_4") (pintype "bidirectional"))
      (node (ref "IMU") (pin "6") (pinfunction "GNDIO_6") (pintype "bidirectional"))
      (node (ref "IMU") (pin "7") (pinfunction "PS_7") (pintype "bidirectional"))
      (node (ref "JP1") (pin "2") (pinfunction "2_2") (pintype "passive"))
      (node (ref "JP2") (pin "2") (pinfunction "2_2") (pintype "passive"))
      (node (ref "JST_CONNECTION") (pin "1") (pinfunction "1_1") (pintype "bidirectional"))
      (node (ref "MAGNETOMETER") (pin "6") (pinfunction "GND_1_6") (pintype "bidirectional"))
      (node (ref "MAGNETOMETER") (pin "8") (pinfunction "GND_2_8") (pintype "bidirectional"))
      (node (ref "MICROCONTROLLER") (pin "12") (pinfunction "VSSA/VREF-_12") (pintype "bidirectional"))
      (node (ref "MICROCONTROLLER") (pin "18") (pinfunction "VSS_1_18") (pintype "bidirectional"))
      (node (ref "MICROCONTROLLER") (pin "31") (pinfunction "VSS_2_31") (pintype "bidirectional"))
      (node (ref "MICROCONTROLLER") (pin "47") (pinfunction "VSS_3_47") (pintype "bidirectional"))
      (node (ref "MICROCONTROLLER") (pin "63") (pinfunction "VSS_4_63") (pintype "bidirectional"))
      (node (ref "POWER_MODULE") (pin "2") (pinfunction "GND_2") (pintype "power_in"))
      (node (ref "POWER_MODULE") (pin "7") (pinfunction "GND_7") (pintype "power_in"))
      (node (ref "R5") (pin "2") (pinfunction "2_2") (pintype "passive"))
      (node (ref "S2") (pin "3") (pinfunction "3_3") (pintype "passive"))
      (node (ref "S2") (pin "4") (pinfunction "4_4") (pintype "passive"))
      (node (ref "U1") (pin "9") (pinfunction "EPAD_9") (pintype "passive"))
      (node (ref "USB_COMM_MODE_FILTER") (pin "5") (pinfunction "GND_2_5") (pintype "passive"))
      (node (ref "USB_COMM_MODE_FILTER") (pin "8") (pinfunction "GND_8") (pintype "passive"))
      (node (ref "Y1") (pin "2") (pinfunction "GROUND_2") (pintype "bidirectional"))
    )
    (net (code "52") (name "Net-(BAROMETER-VDD)") (class "Default")
      (node (ref "BAROMETER") (pin "8") (pinfunction "VDD_8") (pintype "bidirectional"))
      (node (ref "C1") (pin "1") (pinfunction "1_1") (pintype "passive"))
      (node (ref "C26") (pin "1") (pinfunction "1_1") (pintype "passive"))
      (node (ref "L7") (pin "2") (pinfunction "2_2") (pintype "passive"))
    )
    (net (code "53") (name "Net-(D1-PadA)") (class "Default")
      (node (ref "D1") (pin "A") (pinfunction "A_A") (pintype "passive"))
      (node (ref "R3") (pin "1") (pinfunction "1_1") (pintype "passive"))
    )
    (net (code "54") (name "Net-(GPS-TIMEPULSE)") (class "Default")
      (node (ref "GPS") (pin "7") (pinfunction "TIMEPULSE_7") (pintype "bidirectional"))
      (node (ref "L4") (pin "2") (pinfunction "2_2") (pintype "passive"))
    )
    (net (code "55") (name "Net-(GPS-VCC)") (class "Default")
      (node (ref "C25") (pin "2") (pinfunction "2_2") (pintype "passive"))
      (node (ref "C28") (pin "2") (pinfunction "2_2") (pintype "passive"))
      (node (ref "GPS") (pin "17") (pinfunction "VCC_17") (pintype "bidirectional"))
      (node (ref "L6") (pin "1") (pinfunction "1_1") (pintype "passive"))
    )
    (net (code "56") (name "Net-(IMU-VDD)") (class "Default")
      (node (ref "C24") (pin "1") (pinfunction "1_1") (pintype "passive"))
      (node (ref "C4") (pin "1") (pinfunction "1_1") (pintype "passive"))
      (node (ref "IMU") (pin "3") (pinfunction "VDD_3") (pintype "bidirectional"))
      (node (ref "L3") (pin "1") (pinfunction "1_1") (pintype "passive"))
    )
    (net (code "57") (name "Net-(MAGNETOMETER-C1)") (class "Default")
      (node (ref "C13") (pin "1") (pinfunction "1_1") (pintype "passive"))
      (node (ref "MAGNETOMETER") (pin "5") (pinfunction "C1_5") (pintype "bidirectional"))
    )
    (net (code "58") (name "Net-(MAGNETOMETER-VDD)") (class "Default")
      (node (ref "C11") (pin "1") (pinfunction "1_1") (pintype "passive"))
      (node (ref "C12") (pin "1") (pinfunction "1_1") (pintype "passive"))
      (node (ref "C27") (pin "1") (pinfunction "1_1") (pintype "passive"))
      (node (ref "L8") (pin "1") (pinfunction "1_1") (pintype "passive"))
      (node (ref "MAGNETOMETER") (pin "9") (pinfunction "VDD_9") (pintype "bidirectional"))
    )
    (net (code "59") (name "Net-(MICROCONTROLLER-PC8)") (class "Default")
      (node (ref "MICROCONTROLLER") (pin "39") (pinfunction "PC8_39") (pintype "bidirectional"))
      (node (ref "R13") (pin "1") (pinfunction "1_1") (pintype "passive"))
    )
    (net (code "60") (name "Net-(MICROCONTROLLER-PC9)") (class "Default")
      (node (ref "MICROCONTROLLER") (pin "40") (pinfunction "PC9_40") (pintype "bidirectional"))
      (node (ref "R12") (pin "1") (pinfunction "1_1") (pintype "passive"))
    )
    (net (code "61") (name "Net-(Y1-OUTPUT)") (class "Default")
      (node (ref "R11") (pin "1") (pinfunction "1_1") (pintype "passive"))
      (node (ref "Y1") (pin "3") (pinfunction "OUTPUT_3") (pintype "bidirectional"))
    )
    (net (code "62") (name "unconnected-(AIRSPEED-NC_1-Pad6)") (class "Default")
      (node (ref "AIRSPEED") (pin "6") (pinfunction "NC_1_6") (pintype "bidirectional"))
    )
    (net (code "63") (name "unconnected-(AIRSPEED-NC_2-Pad7)") (class "Default")
      (node (ref "AIRSPEED") (pin "7") (pinfunction "NC_2_7") (pintype "bidirectional"))
    )
    (net (code "64") (name "unconnected-(AIRSPEED-NC_3-Pad8)") (class "Default")
      (node (ref "AIRSPEED") (pin "8") (pinfunction "NC_3_8") (pintype "bidirectional"))
    )
    (net (code "65") (name "unconnected-(GPS-EP-Pad21)") (class "Default")
      (node (ref "GPS") (pin "21") (pinfunction "EP_21") (pintype "bidirectional"))
    )
    (net (code "66") (name "unconnected-(GPS-EXTINT-Pad19)") (class "Default")
      (node (ref "GPS") (pin "19") (pinfunction "EXTINT_19") (pintype "bidirectional"))
    )
    (net (code "67") (name "unconnected-(GPS-SCL-Pad12)") (class "Default")
      (node (ref "GPS") (pin "12") (pinfunction "SCL_12") (pintype "bidirectional"))
    )
    (net (code "68") (name "unconnected-(GPS-SDA-Pad9)") (class "Default")
      (node (ref "GPS") (pin "9") (pinfunction "SDA_9") (pintype "bidirectional"))
    )
    (net (code "69") (name "unconnected-(IMU-NC-Pad2)") (class "Default")
      (node (ref "IMU") (pin "2") (pinfunction "NC_2") (pintype "no_connect"))
    )
    (net (code "70") (name "unconnected-(MAGNETOMETER-NC_1-Pad2)") (class "Default")
      (node (ref "MAGNETOMETER") (pin "2") (pinfunction "NC_1_2") (pintype "bidirectional"))
    )
    (net (code "71") (name "unconnected-(MAGNETOMETER-NC_2-Pad11)") (class "Default")
      (node (ref "MAGNETOMETER") (pin "11") (pinfunction "NC_2_11") (pintype "bidirectional"))
    )
    (net (code "72") (name "unconnected-(MAGNETOMETER-NC_3-Pad12)") (class "Default")
      (node (ref "MAGNETOMETER") (pin "12") (pinfunction "NC_3_12") (pintype "bidirectional"))
    )
    (net (code "73") (name "unconnected-(MICROCONTROLLER-PA2-Pad16)") (class "Default")
      (node (ref "MICROCONTROLLER") (pin "16") (pinfunction "PA2_16") (pintype "bidirectional"))
    )
    (net (code "74") (name "unconnected-(MICROCONTROLLER-PA3-Pad17)") (class "Default")
      (node (ref "MICROCONTROLLER") (pin "17") (pinfunction "PA3_17") (pintype "bidirectional"))
    )
    (net (code "75") (name "unconnected-(MICROCONTROLLER-PA8-Pad41)") (class "Default")
      (node (ref "MICROCONTROLLER") (pin "41") (pinfunction "PA8_41") (pintype "bidirectional"))
    )
    (net (code "76") (name "unconnected-(MICROCONTROLLER-PA9-Pad42)") (class "Default")
      (node (ref "MICROCONTROLLER") (pin "42") (pinfunction "PA9_42") (pintype "bidirectional"))
    )
    (net (code "77") (name "unconnected-(MICROCONTROLLER-PA10-Pad43)") (class "Default")
      (node (ref "MICROCONTROLLER") (pin "43") (pinfunction "PA10_43") (pintype "bidirectional"))
    )
    (net (code "78") (name "unconnected-(MICROCONTROLLER-PA15-Pad50)") (class "Default")
      (node (ref "MICROCONTROLLER") (pin "50") (pinfunction "PA15_50") (pintype "bidirectional"))
    )
    (net (code "79") (name "unconnected-(MICROCONTROLLER-PB0-Pad26)") (class "Default")
      (node (ref "MICROCONTROLLER") (pin "26") (pinfunction "PB0_26") (pintype "bidirectional"))
    )
    (net (code "80") (name "unconnected-(MICROCONTROLLER-PB1-Pad27)") (class "Default")
      (node (ref "MICROCONTROLLER") (pin "27") (pinfunction "PB1_27") (pintype "bidirectional"))
    )
    (net (code "81") (name "unconnected-(MICROCONTROLLER-PB4-Pad56)") (class "Default")
      (node (ref "MICROCONTROLLER") (pin "56") (pinfunction "PB4_56") (pintype "bidirectional"))
    )
    (net (code "82") (name "unconnected-(MICROCONTROLLER-PB5-Pad57)") (class "Default")
      (node (ref "MICROCONTROLLER") (pin "57") (pinfunction "PB5_57") (pintype "bidirectional"))
    )
    (net (code "83") (name "unconnected-(MICROCONTROLLER-PB12-Pad33)") (class "Default")
      (node (ref "MICROCONTROLLER") (pin "33") (pinfunction "PB12_33") (pintype "bidirectional"))
    )
    (net (code "84") (name "unconnected-(MICROCONTROLLER-PC2-Pad10)") (class "Default")
      (node (ref "MICROCONTROLLER") (pin "10") (pinfunction "PC2_10") (pintype "bidirectional"))
    )
    (net (code "85") (name "unconnected-(MICROCONTROLLER-PC4-Pad24)") (class "Default")
      (node (ref "MICROCONTROLLER") (pin "24") (pinfunction "PC4_24") (pintype "bidirectional"))
    )
    (net (code "86") (name "unconnected-(MICROCONTROLLER-PC5-Pad25)") (class "Default")
      (node (ref "MICROCONTROLLER") (pin "25") (pinfunction "PC5_25") (pintype "bidirectional"))
    )
    (net (code "87") (name "unconnected-(MICROCONTROLLER-PC6-Pad37)") (class "Default")
      (node (ref "MICROCONTROLLER") (pin "37") (pinfunction "PC6_37") (pintype "bidirectional"))
    )
    (net (code "88") (name "unconnected-(MICROCONTROLLER-PC7-Pad38)") (class "Default")
      (node (ref "MICROCONTROLLER") (pin "38") (pinfunction "PC7_38") (pintype "bidirectional"))
    )
    (net (code "89") (name "unconnected-(MICROCONTROLLER-PC12-Pad53)") (class "Default")
      (node (ref "MICROCONTROLLER") (pin "53") (pinfunction "PC12_53") (pintype "bidirectional"))
    )
    (net (code "90") (name "unconnected-(MICROCONTROLLER-PC13-Pad2)") (class "Default")
      (node (ref "MICROCONTROLLER") (pin "2") (pinfunction "PC13_2") (pintype "bidirectional"))
    )
    (net (code "91") (name "unconnected-(MICROCONTROLLER-PC14-OSC32_IN-Pad3)") (class "Default")
      (node (ref "MICROCONTROLLER") (pin "3") (pinfunction "PC14-OSC32_IN_3") (pintype "bidirectional"))
    )
    (net (code "92") (name "unconnected-(MICROCONTROLLER-PC15-OSC32_OUT-Pad4)") (class "Default")
      (node (ref "MICROCONTROLLER") (pin "4") (pinfunction "PC15-OSC32_OUT_4") (pintype "bidirectional"))
    )
    (net (code "93") (name "unconnected-(MICROCONTROLLER-PD2-Pad54)") (class "Default")
      (node (ref "MICROCONTROLLER") (pin "54") (pinfunction "PD2_54") (pintype "bidirectional"))
    )
    (net (code "94") (name "unconnected-(MICROCONTROLLER-PH1-OSC_OUT-Pad6)") (class "Default")
      (node (ref "MICROCONTROLLER") (pin "6") (pinfunction "PH1-OSC_OUT_6") (pintype "bidirectional"))
    )
    (net (code "95") (name "unconnected-(USB_COMM_MODE_FILTER-ID-Pad4)") (class "Default")
      (node (ref "USB_COMM_MODE_FILTER") (pin "4") (pinfunction "ID_4") (pintype "passive"))
    )
  )
)
